# Sensor_Dio_Faziko_Pratama.net
KiCad netlist of a schematic drawn in EAGLE
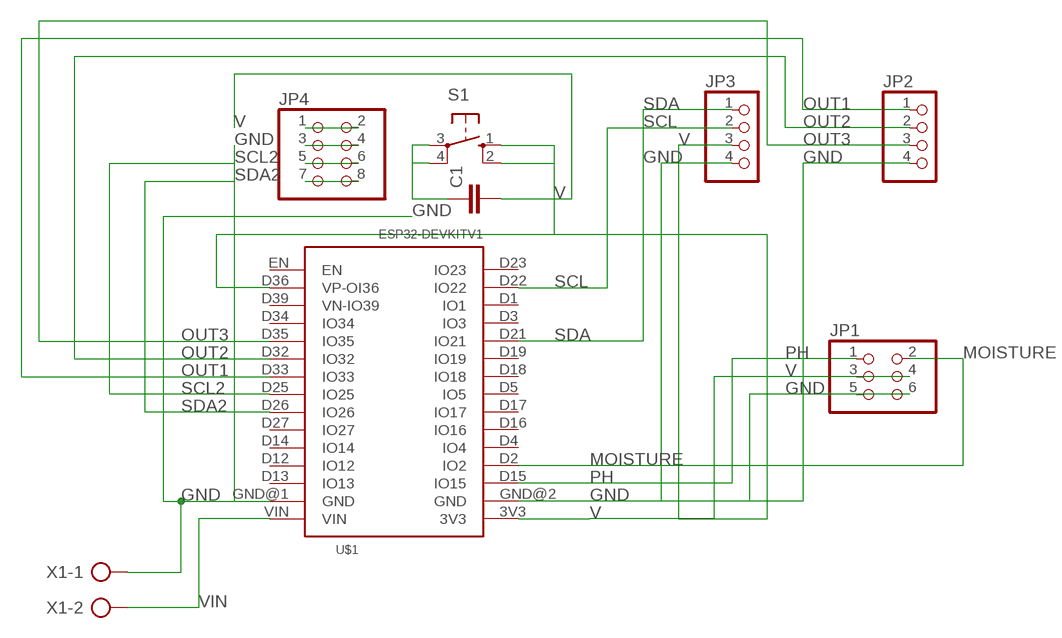
[diagram p0: schematic, sheet 1]

(export (version "E")
  (design (tool "Eeschema 10.0.6"))
  (components
    (comp (ref "C1")
      (value "C-EU050-030X075")
      (footprint "eagle-import:C050-030X075")
      (libsource (lib "eagle-import") (part "C-EU050-030X075"))
    )
    (comp (ref "JP1")
      (value "PINHD-2X3")
      (footprint "eagle-import:2X03")
      (libsource (lib "eagle-import") (part "PINHD-2X3"))
    )
    (comp (ref "JP2")
      (value "PINHD-1X4")
      (footprint "eagle-import:1X04")
      (libsource (lib "eagle-import") (part "PINHD-1X4"))
    )
    (comp (ref "JP3")
      (value "PINHD-1X4")
      (footprint "eagle-import:1X04")
      (libsource (lib "eagle-import") (part "PINHD-1X4"))
    )
    (comp (ref "JP4")
      (value "PINHD-2X4")
      (footprint "eagle-import:2X04")
      (libsource (lib "eagle-import") (part "PINHD-2X4"))
    )
    (comp (ref "S1")
      (value "10-XX")
      (footprint "eagle-import:B3F-10XX")
      (fields (field (name "MPN") "B3F-1000"))
      (libsource (lib "eagle-import") (part "10-XX"))
    )
    (comp (ref "U$1")
      (value "ESP32DEVKITV1")
      (footprint "eagle-import:ESP32-DEVKITV1")
      (libsource (lib "eagle-import") (part "ESP32DEVKITV1"))
    )
    (comp (ref "X1")
      (value "AK300/2")
      (footprint "eagle-import:AK300_2")
      (libsource (lib "eagle-import") (part "AK300/2"))
    )
  )
  (nets
    (net (code "1") (name "/GND") (class "Default")
      (node (ref "C1") (pin "1") (pinfunction "1_1") (pintype "passive"))
      (node (ref "JP1") (pin "5") (pinfunction "5_5") (pintype "passive"))
      (node (ref "JP1") (pin "6") (pinfunction "6_6") (pintype "passive"))
      (node (ref "JP2") (pin "4") (pinfunction "4_4") (pintype "passive"))
      (node (ref "JP3") (pin "4") (pinfunction "4_4") (pintype "passive"))
      (node (ref "JP4") (pin "3") (pinfunction "3_3") (pintype "passive"))
      (node (ref "JP4") (pin "4") (pinfunction "4_4") (pintype "passive"))
      (node (ref "S1") (pin "3") (pinfunction "P_3") (pintype "passive"))
      (node (ref "S1") (pin "4") (pinfunction "P1_4") (pintype "passive"))
      (node (ref "U$1") (pin "GND@1") (pinfunction "GND_GND@1") (pintype "bidirectional"))
      (node (ref "U$1") (pin "GND@2") (pinfunction "GND_GND@2") (pintype "bidirectional"))
      (node (ref "X1") (pin "1") (pinfunction "KL_1") (pintype "passive"))
    )
    (net (code "2") (name "/MOISTURE") (class "Default")
      (node (ref "JP1") (pin "2") (pinfunction "2_2") (pintype "passive"))
      (node (ref "U$1") (pin "D2") (pinfunction "IO2_D2") (pintype "bidirectional"))
    )
    (net (code "3") (name "/OUT1") (class "Default")
      (node (ref "JP2") (pin "1") (pinfunction "1_1") (pintype "passive"))
      (node (ref "U$1") (pin "D33") (pinfunction "IO33_D33") (pintype "bidirectional"))
    )
    (net (code "4") (name "/OUT2") (class "Default")
      (node (ref "JP2") (pin "2") (pinfunction "2_2") (pintype "passive"))
      (node (ref "U$1") (pin "D32") (pinfunction "IO32_D32") (pintype "bidirectional"))
    )
    (net (code "5") (name "/OUT3") (class "Default")
      (node (ref "JP2") (pin "3") (pinfunction "3_3") (pintype "passive"))
      (node (ref "U$1") (pin "D35") (pinfunction "IO35_D35") (pintype "bidirectional"))
    )
    (net (code "6") (name "/PH") (class "Default")
      (node (ref "JP1") (pin "1") (pinfunction "1_1") (pintype "passive"))
      (node (ref "U$1") (pin "D15") (pinfunction "IO15_D15") (pintype "bidirectional"))
    )
    (net (code "7") (name "/SCL") (class "Default")
      (node (ref "JP3") (pin "2") (pinfunction "2_2") (pintype "passive"))
      (node (ref "U$1") (pin "D22") (pinfunction "IO22_D22") (pintype "bidirectional"))
    )
    (net (code "8") (name "/SCL2") (class "Default")
      (node (ref "JP4") (pin "5") (pinfunction "5_5") (pintype "passive"))
      (node (ref "JP4") (pin "6") (pinfunction "6_6") (pintype "passive"))
      (node (ref "U$1") (pin "D25") (pinfunction "IO25_D25") (pintype "bidirectional"))
    )
    (net (code "9") (name "/SDA") (class "Default")
      (node (ref "JP3") (pin "1") (pinfunction "1_1") (pintype "passive"))
      (node (ref "U$1") (pin "D21") (pinfunction "IO21_D21") (pintype "bidirectional"))
    )
    (net (code "10") (name "/SDA2") (class "Default")
      (node (ref "JP4") (pin "7") (pinfunction "7_7") (pintype "passive"))
      (node (ref "JP4") (pin "8") (pinfunction "8_8") (pintype "passive"))
      (node (ref "U$1") (pin "D26") (pinfunction "IO26_D26") (pintype "bidirectional"))
    )
    (net (code "11") (name "/V") (class "Default")
      (node (ref "C1") (pin "2") (pinfunction "2_2") (pintype "passive"))
      (node (ref "JP1") (pin "3") (pinfunction "3_3") (pintype "passive"))
      (node (ref "JP1") (pin "4") (pinfunction "4_4") (pintype "passive"))
      (node (ref "JP3") (pin "3") (pinfunction "3_3") (pintype "passive"))
      (node (ref "JP4") (pin "1") (pinfunction "1_1") (pintype "passive"))
      (node (ref "JP4") (pin "2") (pinfunction "2_2") (pintype "passive"))
      (node (ref "S1") (pin "1") (pinfunction "S_1") (pintype "passive"))
      (node (ref "S1") (pin "2") (pinfunction "S1_2") (pintype "passive"))
      (node (ref "U$1") (pin "3V3") (pinfunction "3V3_3V3") (pintype "bidirectional"))
      (node (ref "U$1") (pin "D36") (pinfunction "VP-OI36_D36") (pintype "bidirectional"))
    )
    (net (code "12") (name "/VIN") (class "Default")
      (node (ref "U$1") (pin "VIN") (pinfunction "VIN_VIN") (pintype "bidirectional"))
      (node (ref "X1") (pin "2") (pinfunction "KL_2") (pintype "passive"))
    )
    (net (code "13") (name "unconnected-(U$1-IO1-PadD1)") (class "Default")
      (node (ref "U$1") (pin "D1") (pinfunction "IO1_D1") (pintype "bidirectional"))
    )
    (net (code "14") (name "unconnected-(U$1-IO3-PadD3)") (class "Default")
      (node (ref "U$1") (pin "D3") (pinfunction "IO3_D3") (pintype "bidirectional"))
    )
    (net (code "15") (name "unconnected-(U$1-IO4-PadD4)") (class "Default")
      (node (ref "U$1") (pin "D4") (pinfunction "IO4_D4") (pintype "bidirectional"))
    )
    (net (code "16") (name "unconnected-(U$1-IO5-PadD5)") (class "Default")
      (node (ref "U$1") (pin "D5") (pinfunction "IO5_D5") (pintype "bidirectional"))
    )
    (net (code "17") (name "unconnected-(U$1-IO12-PadD12)") (class "Default")
      (node (ref "U$1") (pin "D12") (pinfunction "IO12_D12") (pintype "bidirectional"))
    )
    (net (code "18") (name "unconnected-(U$1-IO13-PadD13)") (class "Default")
      (node (ref "U$1") (pin "D13") (pinfunction "IO13_D13") (pintype "bidirectional"))
    )
    (net (code "19") (name "unconnected-(U$1-IO14-PadD14)") (class "Default")
      (node (ref "U$1") (pin "D14") (pinfunction "IO14_D14") (pintype "bidirectional"))
    )
    (net (code "20") (name "unconnected-(U$1-IO16-PadD16)") (class "Default")
      (node (ref "U$1") (pin "D16") (pinfunction "IO16_D16") (pintype "bidirectional"))
    )
    (net (code "21") (name "unconnected-(U$1-IO17-PadD17)") (class "Default")
      (node (ref "U$1") (pin "D17") (pinfunction "IO17_D17") (pintype "bidirectional"))
    )
    (net (code "22") (name "unconnected-(U$1-IO18-PadD18)") (class "Default")
      (node (ref "U$1") (pin "D18") (pinfunction "IO18_D18") (pintype "bidirectional"))
    )
    (net (code "23") (name "unconnected-(U$1-IO19-PadD19)") (class "Default")
      (node (ref "U$1") (pin "D19") (pinfunction "IO19_D19") (pintype "bidirectional"))
    )
    (net (code "24") (name "unconnected-(U$1-IO23-PadD23)") (class "Default")
      (node (ref "U$1") (pin "D23") (pinfunction "IO23_D23") (pintype "bidirectional"))
    )
    (net (code "25") (name "unconnected-(U$1-IO27-PadD27)") (class "Default")
      (node (ref "U$1") (pin "D27") (pinfunction "IO27_D27") (pintype "bidirectional"))
    )
    (net (code "26") (name "unconnected-(U$1-IO34-PadD34)") (class "Default")
      (node (ref "U$1") (pin "D34") (pinfunction "IO34_D34") (pintype "bidirectional"))
    )
    (net (code "27") (name "unconnected-(U$1-PadEN)") (class "Default")
      (node (ref "U$1") (pin "EN") (pinfunction "EN_EN") (pintype "bidirectional"))
    )
    (net (code "28") (name "unconnected-(U$1-VN-IO39-PadD39)") (class "Default")
      (node (ref "U$1") (pin "D39") (pinfunction "VN-IO39_D39") (pintype "bidirectional"))
    )
  )
)
